# schema.net
KiCad netlist of a schematic drawn in Altium Designer
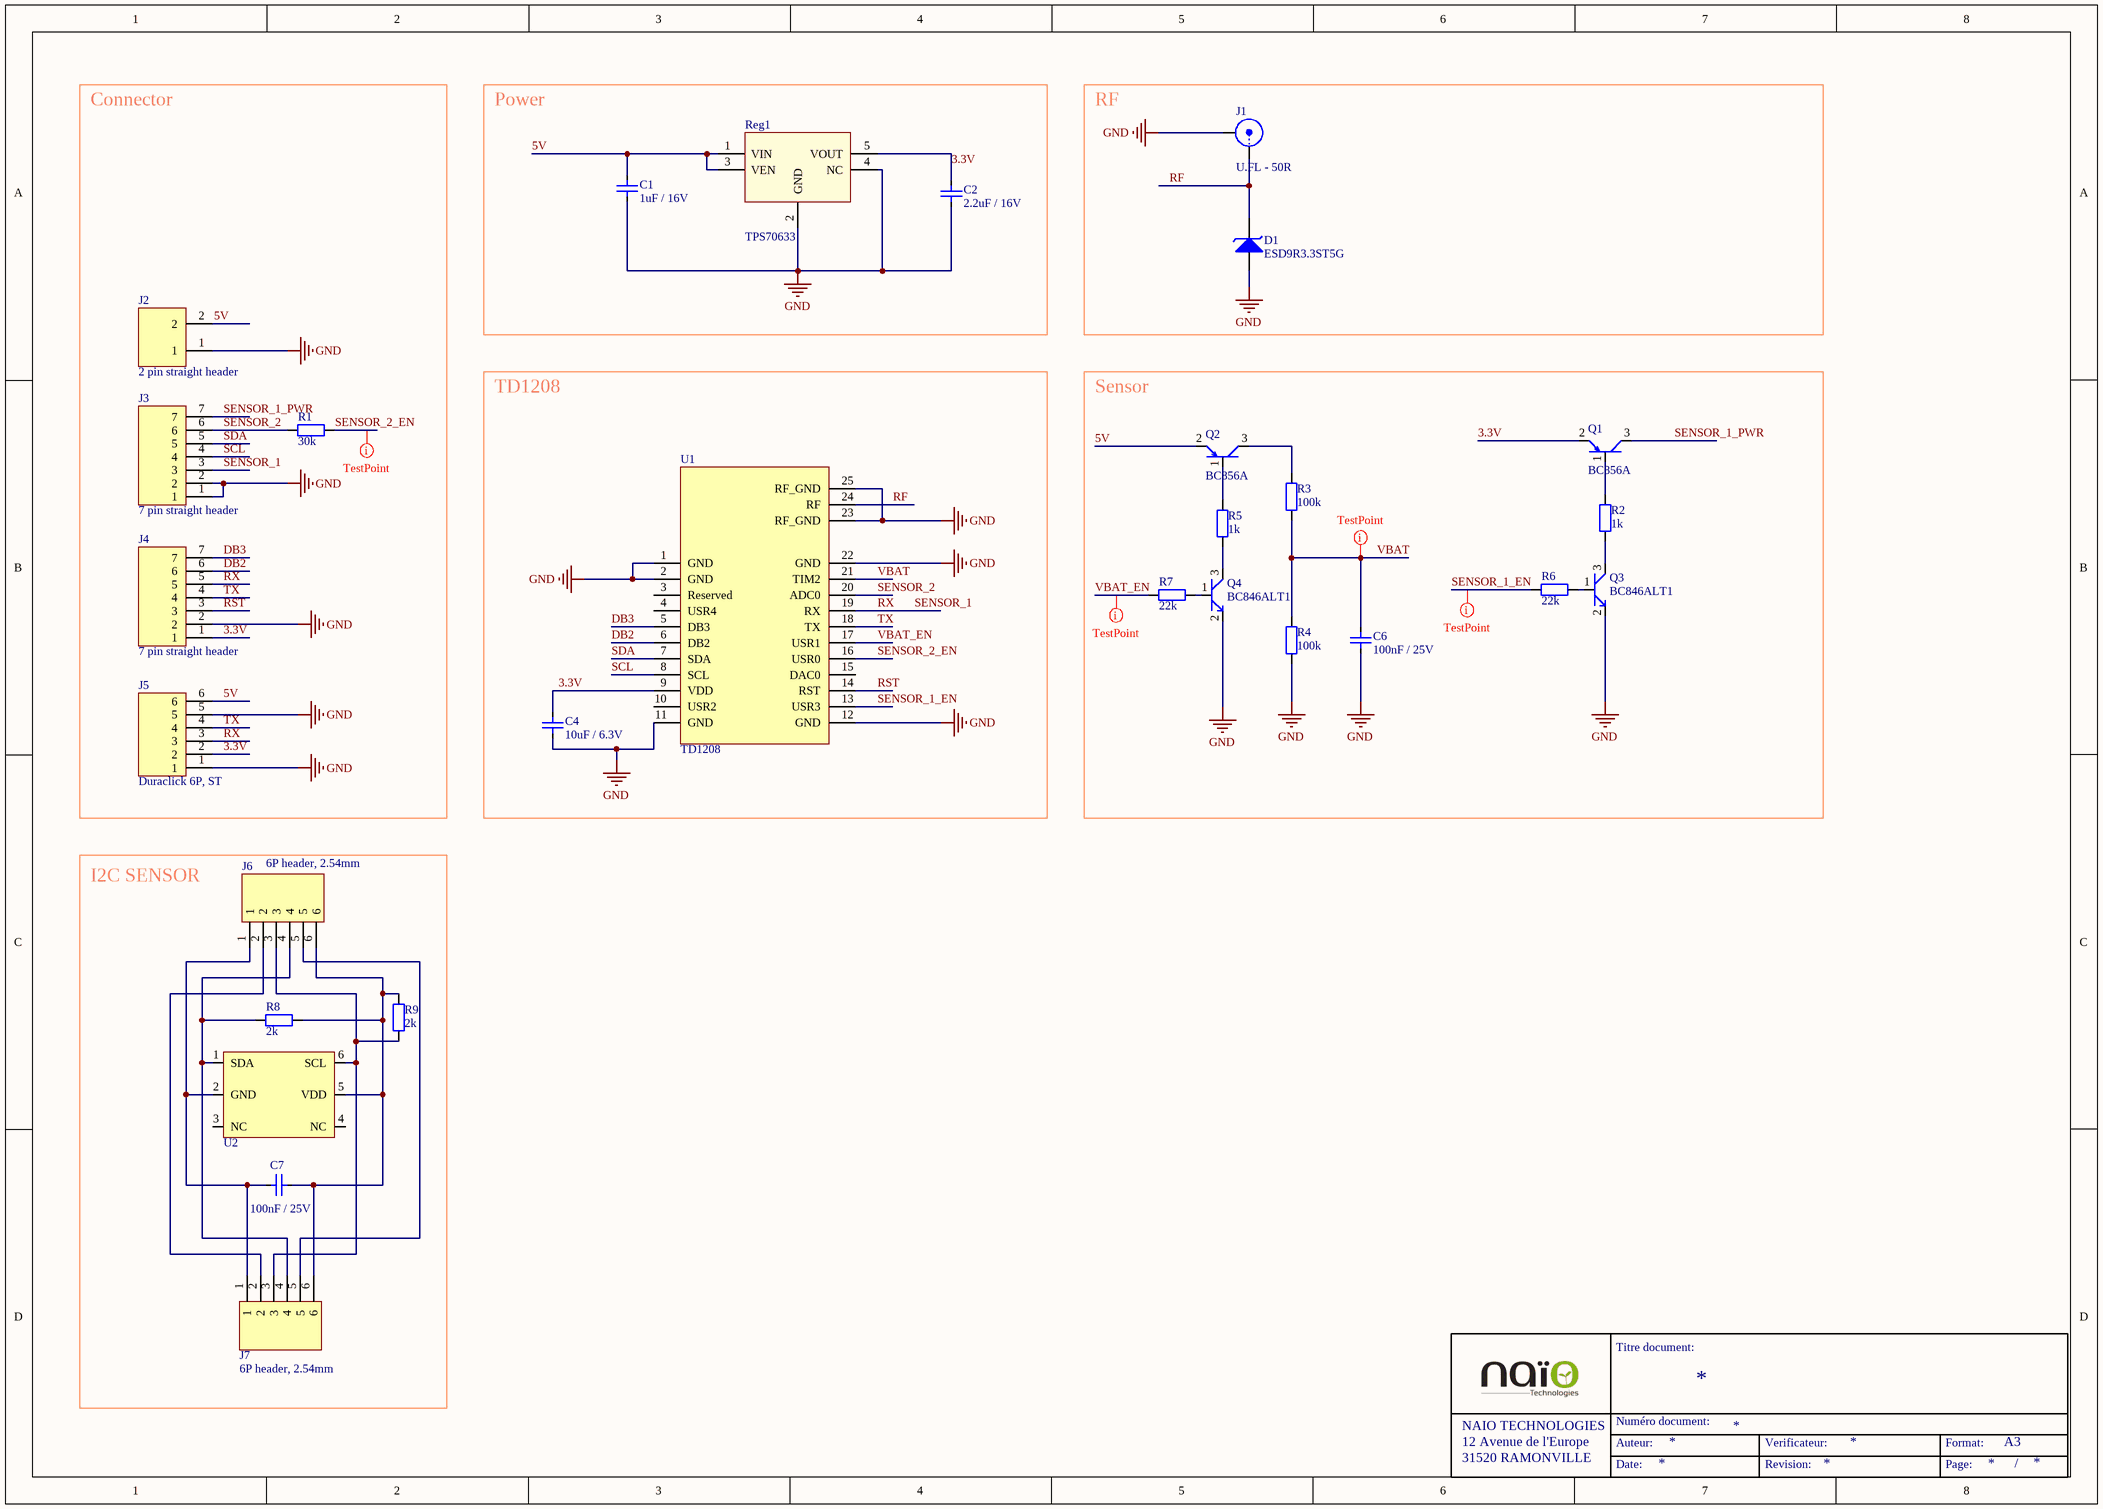
[diagram p0: schema.SchDoc]

(export (version "E")
  (design (tool "Eeschema 10.0.6"))
  (components
    (comp (ref "C1")
      (value "CAP-SMD")
      (footprint "C0805-STD")
      (description "0805 1uF / 16V X7R ceramic capacitor")
      (fields
        (field (name "DISPLAYED REFERENCE") "1uF / 16V")
        (field (name "TOLERANCE") "+/- 10%")
        (field (name "MANUFACTURER") "Kemet")
      )
      (libsource (lib "lib_NAIO") (part "CAP-SMD"))
    )
    (comp (ref "C2")
      (value "CAP-SMD")
      (footprint "C0805-STD")
      (description "0805 2.2uF / 16V X7R ceramic capacitor")
      (fields
        (field (name "DISPLAYED REFERENCE") "2.2uF / 16V")
        (field (name "TOLERANCE") "+/- 10%")
        (field (name "MANUFACTURER") "Kemet")
      )
      (libsource (lib "lib_NAIO") (part "CAP-SMD"))
    )
    (comp (ref "C4")
      (value "CAP-SMD")
      (footprint "C0805-STD")
      (description "0805 10uF / 6.3V X5R ceramic capacitor")
      (fields
        (field (name "DISPLAYED REFERENCE") "10uF / 6.3V")
        (field (name "TOLERANCE") "+/- 10%")
        (field (name "MANUFACTURER") "Kemet")
      )
      (libsource (lib "lib_NAIO") (part "CAP-SMD"))
    )
    (comp (ref "C6")
      (value "CAP-SMD")
      (footprint "C0603-STD")
      (description "0603 100nF /25V X7R ceramic capacitor")
      (fields
        (field (name "DISPLAYED REFERENCE") "100nF / 25V")
        (field (name "TOLERANCE") "+/- 10%")
        (field (name "MANUFACTURER") "Kemet")
      )
      (libsource (lib "lib_NAIO") (part "CAP-SMD"))
    )
    (comp (ref "C7")
      (value "CAP-SMD")
      (footprint "C0603-STD")
      (description "0603 100nF /25V X7R ceramic capacitor")
      (fields
        (field (name "DISPLAYED REFERENCE") "100nF / 25V")
        (field (name "TOLERANCE") "+/- 10%")
        (field (name "MANUFACTURER") "Kemet")
      )
      (libsource (lib "lib_NAIO") (part "CAP-SMD"))
    )
    (comp (ref "D1")
      (value "ESD9R33ST5G-SOD923")
      (footprint "SOD923-SPE-ESD9R33ST5G")
      (description "Diode TVS 3.3V in SMD package")
      (fields (field (name "DISPLAYED REFERENCE") "ESD9R3.3ST5G") (field (name "MANUFACTURER") "ON semi"))
      (libsource (lib "lib_NAIO") (part "ESD9R33ST5G-SOD923"))
    )
    (comp (ref "J1")
      (value "COAX-RF")
      (footprint "UFL_R_SMT1-STD")
      (description "UF.L-R-SMT-1 SMD connector")
      (fields (field (name "DISPLAYED REFERENCE") "U.FL - 50R") (field (name "MANUFACTURER") "HRS"))
      (libsource (lib "lib_NAIO") (part "COAX-RF"))
    )
    (comp (ref "J2")
      (value "CONN-STD-2P_1ROW")
      (footprint "CONN-STD-2_254_STRAIGHT_HEADER")
      (description "2 PIN, 2.54mm pitch, 1 row, straight, male")
      (fields
        (field (name "DISPLAYED REFERENCE") "2 pin straight header")
        (field (name "MANUFACTURER") "TE connectivity")
      )
      (libsource (lib "lib_NAIO") (part "CONN-STD-2P_1ROW"))
    )
    (comp (ref "J3")
      (value "CONN-STD-7P_1ROW")
      (footprint "CONN-STD-7_254_STRAIGHT_HEADER")
      (description "7 PIN, 2.54mm pitch, 1 row, straight, male")
      (fields
        (field (name "DISPLAYED REFERENCE") "7 pin straight header")
        (field (name "MANUFACTURER") "TE connectivity")
      )
      (libsource (lib "lib_NAIO") (part "CONN-STD-7P_1ROW"))
    )
    (comp (ref "J4")
      (value "CONN-STD-7P_1ROW")
      (footprint "CONN-STD-7_254_STRAIGHT_HEADER")
      (description "7 PIN, 2.54mm pitch, 1 row, straight, male")
      (fields
        (field (name "DISPLAYED REFERENCE") "7 pin straight header")
        (field (name "MANUFACTURER") "TE connectivity")
      )
      (libsource (lib "lib_NAIO") (part "CONN-STD-7P_1ROW"))
    )
    (comp (ref "J5")
      (value "CONN-STD-6P_1ROW")
      (footprint "CONN-SPE-560020-0620_MOLEX")
      (description "6 pin, 2mm pitch herader, SM, ST")
      (fields (field (name "DISPLAYED REFERENCE") "Duraclick 6P, ST") (field (name "MANUFACTURER") "MOLEX"))
      (libsource (lib "") (part "CONN-STD-6P_1ROW_1"))
    )
    (comp (ref "J6")
      (value "CONN-STD-6P_1ROW")
      (footprint "6P_HEADER-STD_TH_1ROW")
      (description "6P, 1 row, 2.54mm header")
      (fields (field (name "DISPLAYED REFERENCE") "6P header, 2.54mm") (field (name "MANUFACTURER") "FCI"))
      (libsource (lib "lib_NAIO") (part "CONN-STD-6P_1ROW"))
    )
    (comp (ref "J7")
      (value "CONN-STD-6P_1ROW")
      (footprint "6P_HEADER-STD_TH_1ROW")
      (description "6P, 1 row, 2.54mm header")
      (fields (field (name "DISPLAYED REFERENCE") "6P header, 2.54mm") (field (name "MANUFACTURER") "FCI"))
      (libsource (lib "") (part "CONN-STD-6P_1ROW_1"))
    )
    (comp (ref "Q1")
      (value "BC856A-SOT23")
      (footprint "SOT23-STD")
      (description "PNP small signal transistor")
      (fields (field (name "DISPLAYED REFERENCE") "BC856A") (field (name "MANUFACTURER") "DIODES"))
      (libsource (lib "lib_NAIO") (part "BC856A-SOT23"))
    )
    (comp (ref "Q2")
      (value "BC856A-SOT23")
      (footprint "SOT23-STD")
      (description "PNP small signal transistor")
      (fields (field (name "DISPLAYED REFERENCE") "BC856A") (field (name "MANUFACTURER") "DIODES"))
      (libsource (lib "lib_NAIO") (part "BC856A-SOT23"))
    )
    (comp (ref "Q3")
      (value "BC846ALT1-SOT23")
      (footprint "SOT23-STD")
      (description "NPN small signal transistor")
      (fields (field (name "DISPLAYED REFERENCE") "BC846ALT1") (field (name "MANUFACTURER") "ON semi"))
      (libsource (lib "lib_NAIO") (part "BC846ALT1-SOT23"))
    )
    (comp (ref "Q4")
      (value "BC846ALT1-SOT23")
      (footprint "SOT23-STD")
      (description "NPN small signal transistor")
      (fields (field (name "DISPLAYED REFERENCE") "BC846ALT1") (field (name "MANUFACTURER") "ON semi"))
      (libsource (lib "lib_NAIO") (part "BC846ALT1-SOT23"))
    )
    (comp (ref "R1")
      (value "RES-SMD")
      (footprint "R0805-STD")
      (description "30k Ohm 0805 SMD resistor")
      (fields
        (field (name "DISPLAYED REFERENCE") "30k")
        (field (name "TOLERANCE") "1 %")
        (field (name "MANUFACTURER") "Vishay")
      )
      (libsource (lib "") (part "RES-SMD_1"))
    )
    (comp (ref "R2")
      (value "RES-SMD")
      (footprint "R0603-STD")
      (description "1k Ohm 0603 SMD resistor")
      (fields
        (field (name "DISPLAYED REFERENCE") "1k")
        (field (name "TOLERANCE") "1 %")
        (field (name "MANUFACTURER") "Vishay")
      )
      (libsource (lib "lib_NAIO") (part "RES-SMD"))
    )
    (comp (ref "R3")
      (value "RES-SMD")
      (footprint "R0805-STD")
      (description "100k Ohm 0805 SMD resistor")
      (fields
        (field (name "DISPLAYED REFERENCE") "100k")
        (field (name "TOLERANCE") "1 %")
        (field (name "MANUFACTURER") "Vishay")
      )
      (libsource (lib "lib_NAIO") (part "RES-SMD"))
    )
    (comp (ref "R4")
      (value "RES-SMD")
      (footprint "R0805-STD")
      (description "100k Ohm 0805 SMD resistor")
      (fields
        (field (name "DISPLAYED REFERENCE") "100k")
        (field (name "TOLERANCE") "1 %")
        (field (name "MANUFACTURER") "Vishay")
      )
      (libsource (lib "lib_NAIO") (part "RES-SMD"))
    )
    (comp (ref "R5")
      (value "RES-SMD")
      (footprint "R0603-STD")
      (description "1k Ohm 0603 SMD resistor")
      (fields
        (field (name "DISPLAYED REFERENCE") "1k")
        (field (name "TOLERANCE") "1 %")
        (field (name "MANUFACTURER") "Vishay")
      )
      (libsource (lib "lib_NAIO") (part "RES-SMD"))
    )
    (comp (ref "R6")
      (value "RES-SMD")
      (footprint "R0603-STD")
      (description "22k Ohm 0603 SMD resistor")
      (fields
        (field (name "DISPLAYED REFERENCE") "22k")
        (field (name "TOLERANCE") "1 %")
        (field (name "MANUFACTURER") "Vishay")
      )
      (libsource (lib "") (part "RES-SMD_1"))
    )
    (comp (ref "R7")
      (value "RES-SMD")
      (footprint "R0603-STD")
      (description "22k Ohm 0603 SMD resistor")
      (fields
        (field (name "DISPLAYED REFERENCE") "22k")
        (field (name "TOLERANCE") "1 %")
        (field (name "MANUFACTURER") "Vishay")
      )
      (libsource (lib "") (part "RES-SMD_1"))
    )
    (comp (ref "R8")
      (value "RES-SMD")
      (footprint "R0603-STD")
      (description "2k Ohm 0603 SMD resistor")
      (fields
        (field (name "DISPLAYED REFERENCE") "2k")
        (field (name "TOLERANCE") "1 %")
        (field (name "MANUFACTURER") "Vishay")
      )
      (libsource (lib "") (part "RES-SMD_1"))
    )
    (comp (ref "R9")
      (value "RES-SMD")
      (footprint "R0603-STD")
      (description "2k Ohm 0603 SMD resistor")
      (fields
        (field (name "DISPLAYED REFERENCE") "2k")
        (field (name "TOLERANCE") "1 %")
        (field (name "MANUFACTURER") "Vishay")
      )
      (libsource (lib "lib_NAIO") (part "RES-SMD"))
    )
    (comp (ref "Reg1")
      (value "TPS706-SOT23_5")
      (footprint "SOT23_5-SPE-TPS706")
      (description "3.3V / 200mA LDO voltage regulator")
      (fields (field (name "DISPLAYED REFERENCE") "TPS70633") (field (name "MANUFACTURER") "TI"))
      (libsource (lib "lib_NAIO") (part "TPS706-SOT23_5"))
    )
    (comp (ref "U1")
      (value "TD1208-LGA25")
      (footprint "LGA25-SPE-TD1208")
      (description "Sigfox module")
      (fields (field (name "DISPLAYED REFERENCE") "TD1208") (field (name "MANUFACTURER") "Telecom Design"))
      (libsource (lib "lib_NAIO") (part "TD1208-LGA25"))
    )
    (comp (ref "U2")
      (value "SHT21-DFN6")
      (footprint "DFN6-SPE-SHT21")
      (description "I2C Humidity/Temperature sensor")
      (fields (field (name "MANUFACTURER") "SENSIRION"))
      (libsource (lib "lib_NAIO") (part "SHT21-DFN6"))
    )
  )
  (nets
    (net (code "1") (name "/3.3V") (class "Default")
      (node (ref "C2") (pin "2") (pinfunction "2_2") (pintype "passive"))
      (node (ref "C4") (pin "2") (pinfunction "2_2") (pintype "passive"))
      (node (ref "J4") (pin "1") (pinfunction "1_1") (pintype "passive"))
      (node (ref "J5") (pin "2") (pinfunction "2_2") (pintype "passive"))
      (node (ref "Q1") (pin "2") (pinfunction "In_2") (pintype "passive"))
      (node (ref "Reg1") (pin "5") (pinfunction "VOUT_5") (pintype "passive"))
      (node (ref "U1") (pin "9") (pinfunction "VDD_9") (pintype "passive"))
    )
    (net (code "2") (name "/5V") (class "Default")
      (node (ref "C1") (pin "2") (pinfunction "2_2") (pintype "passive"))
      (node (ref "J2") (pin "2") (pinfunction "2_2") (pintype "passive"))
      (node (ref "J5") (pin "6") (pinfunction "6_6") (pintype "passive"))
      (node (ref "Q2") (pin "2") (pinfunction "In_2") (pintype "passive"))
      (node (ref "Reg1") (pin "1") (pinfunction "VIN_1") (pintype "passive"))
      (node (ref "Reg1") (pin "3") (pinfunction "VEN_3") (pintype "passive"))
    )
    (net (code "3") (name "/DB2") (class "Default")
      (node (ref "J4") (pin "6") (pinfunction "6_6") (pintype "passive"))
      (node (ref "U1") (pin "6") (pinfunction "DB2_6") (pintype "passive"))
    )
    (net (code "4") (name "/DB3") (class "Default")
      (node (ref "J4") (pin "7") (pinfunction "7_7") (pintype "passive"))
      (node (ref "U1") (pin "5") (pinfunction "DB3_5") (pintype "passive"))
    )
    (net (code "5") (name "/RF") (class "Default")
      (node (ref "D1") (pin "K") (pinfunction "K_K") (pintype "passive"))
      (node (ref "J1") (pin "1") (pinfunction "Sig_1") (pintype "passive"))
      (node (ref "U1") (pin "24") (pinfunction "RF_24") (pintype "passive"))
    )
    (net (code "6") (name "/RST") (class "Default")
      (node (ref "J4") (pin "3") (pinfunction "3_3") (pintype "passive"))
      (node (ref "U1") (pin "14") (pinfunction "RST_14") (pintype "passive"))
    )
    (net (code "7") (name "/RX") (class "Default")
      (node (ref "J3") (pin "3") (pinfunction "3_3") (pintype "passive"))
      (node (ref "J4") (pin "5") (pinfunction "5_5") (pintype "passive"))
      (node (ref "J5") (pin "3") (pinfunction "3_3") (pintype "passive"))
      (node (ref "U1") (pin "19") (pinfunction "RX_19") (pintype "passive"))
    )
    (net (code "8") (name "/SCL") (class "Default")
      (node (ref "J3") (pin "4") (pinfunction "4_4") (pintype "passive"))
      (node (ref "U1") (pin "8") (pinfunction "SCL_8") (pintype "passive"))
    )
    (net (code "9") (name "/SDA") (class "Default")
      (node (ref "J3") (pin "5") (pinfunction "5_5") (pintype "passive"))
      (node (ref "U1") (pin "7") (pinfunction "SDA_7") (pintype "passive"))
    )
    (net (code "10") (name "/SENSOR_1_EN") (class "Default")
      (node (ref "R6") (pin "1") (pinfunction "1_1") (pintype "passive"))
      (node (ref "U1") (pin "13") (pinfunction "USR3_13") (pintype "passive"))
    )
    (net (code "11") (name "/SENSOR_1_PWR") (class "Default")
      (node (ref "J3") (pin "7") (pinfunction "7_7") (pintype "passive"))
      (node (ref "Q1") (pin "3") (pinfunction "In_3") (pintype "passive"))
    )
    (net (code "12") (name "/SENSOR_2") (class "Default")
      (node (ref "J3") (pin "6") (pinfunction "6_6") (pintype "passive"))
      (node (ref "R1") (pin "1") (pinfunction "1_1") (pintype "passive"))
      (node (ref "U1") (pin "20") (pinfunction "ADC0_20") (pintype "passive"))
    )
    (net (code "13") (name "/SENSOR_2_EN") (class "Default")
      (node (ref "R1") (pin "2") (pinfunction "2_2") (pintype "passive"))
      (node (ref "U1") (pin "16") (pinfunction "USR0_16") (pintype "passive"))
    )
    (net (code "14") (name "/TX") (class "Default")
      (node (ref "J4") (pin "4") (pinfunction "4_4") (pintype "passive"))
      (node (ref "J5") (pin "4") (pinfunction "4_4") (pintype "passive"))
      (node (ref "U1") (pin "18") (pinfunction "TX_18") (pintype "passive"))
    )
    (net (code "15") (name "/VBAT") (class "Default")
      (node (ref "C6") (pin "2") (pinfunction "2_2") (pintype "passive"))
      (node (ref "R3") (pin "1") (pinfunction "1_1") (pintype "passive"))
      (node (ref "R4") (pin "2") (pinfunction "2_2") (pintype "passive"))
      (node (ref "U1") (pin "21") (pinfunction "TIM2_21") (pintype "passive"))
    )
    (net (code "16") (name "/VBAT_EN") (class "Default")
      (node (ref "R7") (pin "1") (pinfunction "1_1") (pintype "passive"))
      (node (ref "U1") (pin "17") (pinfunction "USR1_17") (pintype "passive"))
    )
    (net (code "17") (name "GND") (class "Default")
      (node (ref "C1") (pin "1") (pinfunction "1_1") (pintype "passive"))
      (node (ref "C2") (pin "1") (pinfunction "1_1") (pintype "passive"))
      (node (ref "C4") (pin "1") (pinfunction "1_1") (pintype "passive"))
      (node (ref "C6") (pin "1") (pinfunction "1_1") (pintype "passive"))
      (node (ref "D1") (pin "A") (pinfunction "A_A") (pintype "passive"))
      (node (ref "J1") (pin "2") (pinfunction "GND_2") (pintype "passive"))
      (node (ref "J2") (pin "1") (pinfunction "1_1") (pintype "passive"))
      (node (ref "J3") (pin "1") (pinfunction "1_1") (pintype "passive"))
      (node (ref "J3") (pin "2") (pinfunction "2_2") (pintype "passive"))
      (node (ref "J4") (pin "2") (pinfunction "2_2") (pintype "passive"))
      (node (ref "J5") (pin "1") (pinfunction "1_1") (pintype "passive"))
      (node (ref "J5") (pin "5") (pinfunction "5_5") (pintype "passive"))
      (node (ref "Q3") (pin "2") (pinfunction "In_2") (pintype "passive"))
      (node (ref "Q4") (pin "2") (pinfunction "In_2") (pintype "passive"))
      (node (ref "R4") (pin "1") (pinfunction "1_1") (pintype "passive"))
      (node (ref "Reg1") (pin "2") (pinfunction "GND_2") (pintype "passive"))
      (node (ref "Reg1") (pin "4") (pinfunction "NC_4") (pintype "passive"))
      (node (ref "U1") (pin "1") (pinfunction "GND_1") (pintype "passive"))
      (node (ref "U1") (pin "11") (pinfunction "GND_11") (pintype "passive"))
      (node (ref "U1") (pin "12") (pinfunction "GND_12") (pintype "passive"))
      (node (ref "U1") (pin "2") (pinfunction "GND_2") (pintype "passive"))
      (node (ref "U1") (pin "22") (pinfunction "GND_22") (pintype "passive"))
      (node (ref "U1") (pin "23") (pinfunction "RF_GND_23") (pintype "passive"))
      (node (ref "U1") (pin "25") (pinfunction "RF_GND_25") (pintype "passive"))
    )
    (net (code "18") (name "Net-(J6-Pad2)") (class "Default")
      (node (ref "J6") (pin "2") (pinfunction "2_2") (pintype "passive"))
      (node (ref "J7") (pin "2") (pinfunction "2_2") (pintype "passive"))
    )
    (net (code "19") (name "Net-(J6-Pad5)") (class "Default")
      (node (ref "J6") (pin "5") (pinfunction "5_5") (pintype "passive"))
      (node (ref "J7") (pin "5") (pinfunction "5_5") (pintype "passive"))
    )
    (net (code "20") (name "Net-(Q1-In-Pad1)") (class "Default")
      (node (ref "Q1") (pin "1") (pinfunction "In_1") (pintype "passive"))
      (node (ref "R2") (pin "2") (pinfunction "2_2") (pintype "passive"))
    )
    (net (code "21") (name "Net-(Q2-In-Pad1)") (class "Default")
      (node (ref "Q2") (pin "1") (pinfunction "In_1") (pintype "passive"))
      (node (ref "R5") (pin "2") (pinfunction "2_2") (pintype "passive"))
    )
    (net (code "22") (name "Net-(Q2-In-Pad3)") (class "Default")
      (node (ref "Q2") (pin "3") (pinfunction "In_3") (pintype "passive"))
      (node (ref "R3") (pin "2") (pinfunction "2_2") (pintype "passive"))
    )
    (net (code "23") (name "Net-(Q3-In-Pad1)") (class "Default")
      (node (ref "Q3") (pin "1") (pinfunction "In_1") (pintype "passive"))
      (node (ref "R6") (pin "2") (pinfunction "2_2") (pintype "passive"))
    )
    (net (code "24") (name "Net-(Q3-In-Pad3)") (class "Default")
      (node (ref "Q3") (pin "3") (pinfunction "In_3") (pintype "passive"))
      (node (ref "R2") (pin "1") (pinfunction "1_1") (pintype "passive"))
    )
    (net (code "25") (name "Net-(Q4-In-Pad1)") (class "Default")
      (node (ref "Q4") (pin "1") (pinfunction "In_1") (pintype "passive"))
      (node (ref "R7") (pin "2") (pinfunction "2_2") (pintype "passive"))
    )
    (net (code "26") (name "Net-(Q4-In-Pad3)") (class "Default")
      (node (ref "Q4") (pin "3") (pinfunction "In_3") (pintype "passive"))
      (node (ref "R5") (pin "1") (pinfunction "1_1") (pintype "passive"))
    )
    (net (code "27") (name "Net-(U2-GND)") (class "Default")
      (node (ref "C7") (pin "1") (pinfunction "1_1") (pintype "passive"))
      (node (ref "J6") (pin "1") (pinfunction "1_1") (pintype "passive"))
      (node (ref "J7") (pin "1") (pinfunction "1_1") (pintype "passive"))
      (node (ref "U2") (pin "2") (pinfunction "GND_2") (pintype "passive"))
    )
    (net (code "28") (name "Net-(U2-SCL)") (class "Default")
      (node (ref "J6") (pin "3") (pinfunction "3_3") (pintype "passive"))
      (node (ref "J7") (pin "3") (pinfunction "3_3") (pintype "passive"))
      (node (ref "R9") (pin "1") (pinfunction "1_1") (pintype "passive"))
      (node (ref "U2") (pin "6") (pinfunction "SCL_6") (pintype "passive"))
    )
    (net (code "29") (name "Net-(U2-SDA)") (class "Default")
      (node (ref "J6") (pin "4") (pinfunction "4_4") (pintype "passive"))
      (node (ref "J7") (pin "4") (pinfunction "4_4") (pintype "passive"))
      (node (ref "R8") (pin "1") (pinfunction "1_1") (pintype "passive"))
      (node (ref "U2") (pin "1") (pinfunction "SDA_1") (pintype "passive"))
    )
    (net (code "30") (name "Net-(U2-VDD)") (class "Default")
      (node (ref "C7") (pin "2") (pinfunction "2_2") (pintype "passive"))
      (node (ref "J6") (pin "6") (pinfunction "6_6") (pintype "passive"))
      (node (ref "J7") (pin "6") (pinfunction "6_6") (pintype "passive"))
      (node (ref "R8") (pin "2") (pinfunction "2_2") (pintype "passive"))
      (node (ref "R9") (pin "2") (pinfunction "2_2") (pintype "passive"))
      (node (ref "U2") (pin "5") (pinfunction "VDD_5") (pintype "passive"))
    )
    (net (code "31") (name "unconnected-(U1-DAC0-Pad15)") (class "Default")
      (node (ref "U1") (pin "15") (pinfunction "DAC0_15") (pintype "passive"))
    )
    (net (code "32") (name "unconnected-(U1-Reserved-Pad3)") (class "Default")
      (node (ref "U1") (pin "3") (pinfunction "Reserved_3") (pintype "passive"))
    )
    (net (code "33") (name "unconnected-(U1-USR2-Pad10)") (class "Default")
      (node (ref "U1") (pin "10") (pinfunction "USR2_10") (pintype "passive"))
    )
    (net (code "34") (name "unconnected-(U1-USR4-Pad4)") (class "Default")
      (node (ref "U1") (pin "4") (pinfunction "USR4_4") (pintype "passive"))
    )
    (net (code "35") (name "unconnected-(U2-NC-Pad3)") (class "Default")
      (node (ref "U2") (pin "3") (pinfunction "NC_3") (pintype "passive"))
    )
    (net (code "36") (name "unconnected-(U2-NC-Pad4)") (class "Default")
      (node (ref "U2") (pin "4") (pinfunction "NC_4") (pintype "passive"))
    )
  )
)
